# SCH_ESP-RotaryCell-Main-Carrier-Rev-A1_2.net
KiCad netlist of a schematic drawn in EasyEDA
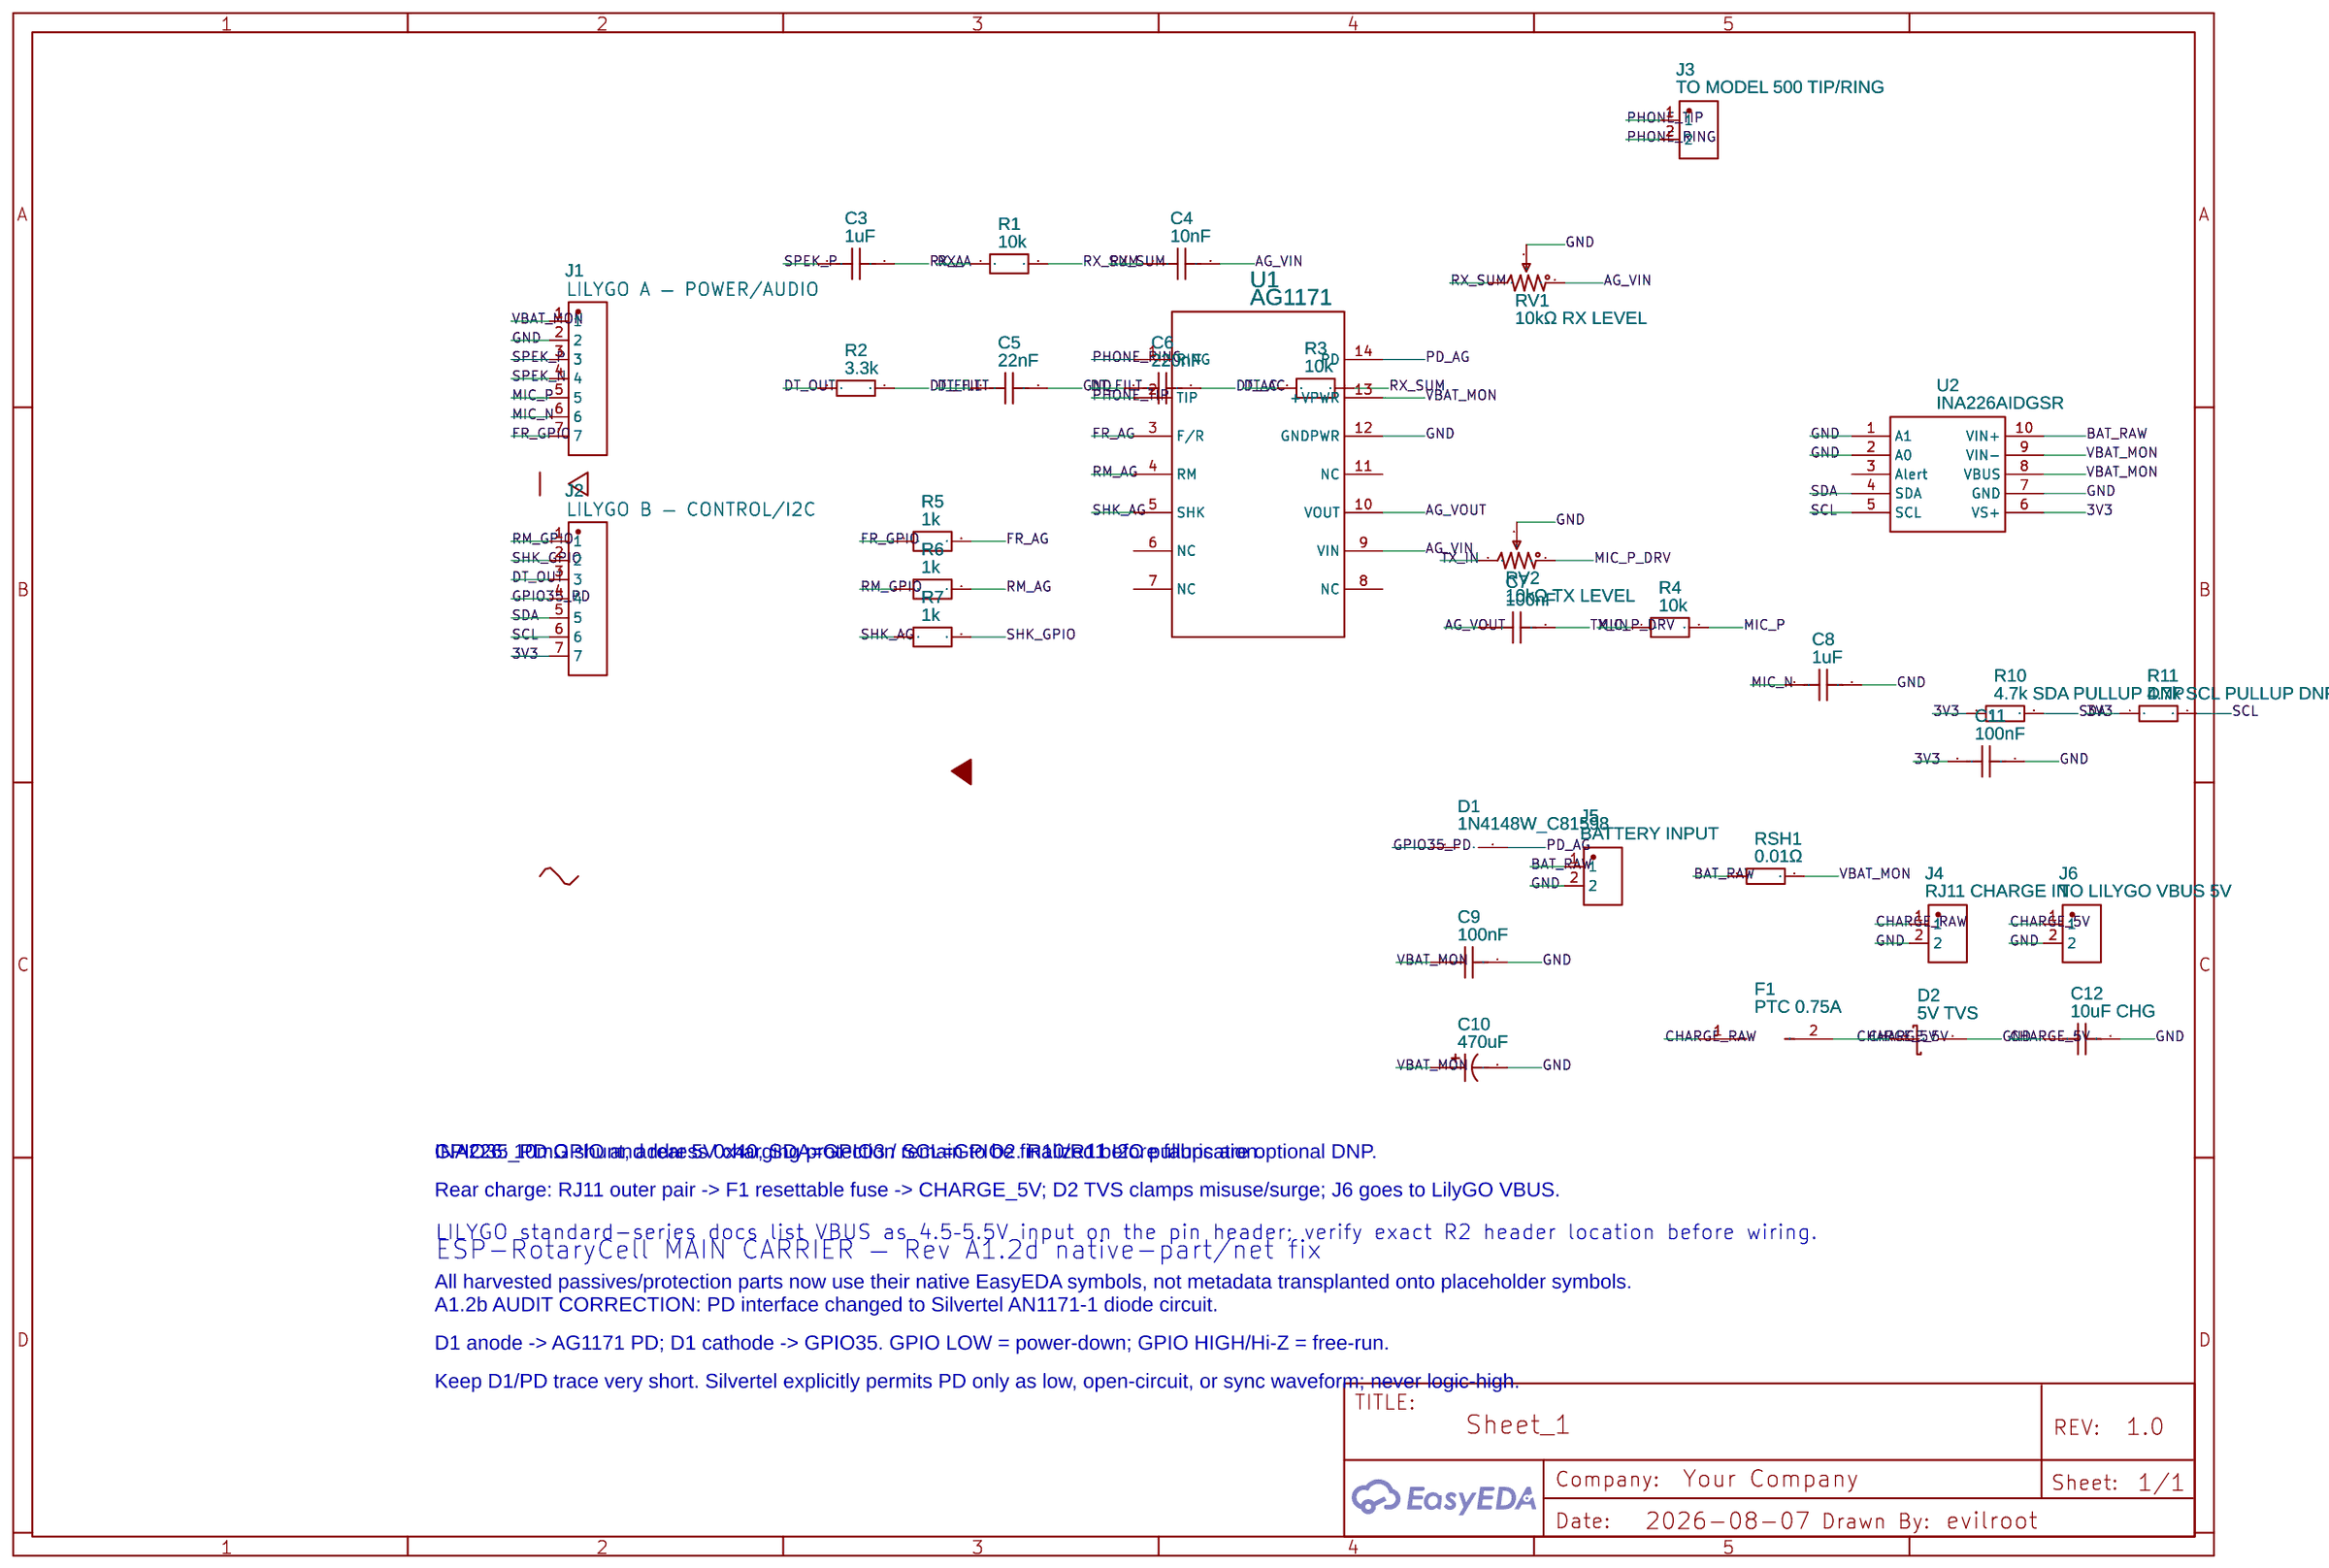
[diagram p0: schematic sheet]

(export (version "E")
  (design (tool "Eeschema 10.0.6"))
  (components
    (comp (ref "C3")
      (value "1uF")
      (fields
        (field (name "Manufacturer Part") "C0805C105K5RACAUTO")
        (field (name "Manufacturer") "KEMET(基美)")
      )
      (libsource (lib "") (part "C0805C105K5RACAUTO"))
    )
    (comp (ref "C4")
      (value "10nF")
      (fields
        (field (name "Manufacturer Part") "CGA0805X7R103J500KT")
        (field (name "Manufacturer") "HRE(芯声)")
      )
      (libsource (lib "") (part "CGA0805X7R103J500KT"))
    )
    (comp (ref "C5")
      (value "22nF")
      (fields
        (field (name "Manufacturer Part") "CGA0805C0G223J500MT")
        (field (name "Manufacturer") "HRE(芯声)")
      )
      (libsource (lib "") (part "CGA0805C0G223J500MT"))
    )
    (comp (ref "C6")
      (value "220nF")
      (fields
        (field (name "Manufacturer Part") "CGA0805X7R224K101MT")
        (field (name "Manufacturer") "HRE(芯声)")
      )
      (libsource (lib "") (part "CGA0805X7R224K101MT"))
    )
    (comp (ref "C7")
      (value "100nF")
      (fields
        (field (name "Manufacturer Part") "CAI0805X7R104K500KT")
        (field (name "Manufacturer") "HRE(芯声)")
      )
      (libsource (lib "") (part "CAI0805X7R104K500KT"))
    )
    (comp (ref "C8")
      (value "1uF")
      (fields
        (field (name "Manufacturer Part") "C0805C105K5RACAUTO")
        (field (name "Manufacturer") "KEMET(基美)")
      )
      (libsource (lib "") (part "C0805C105K5RACAUTO"))
    )
    (comp (ref "C9")
      (value "100nF")
      (fields
        (field (name "Manufacturer Part") "CAI0805X7R104K500KT")
        (field (name "Manufacturer") "HRE(芯声)")
      )
      (libsource (lib "") (part "CAI0805X7R104K500KT"))
    )
    (comp (ref "C10")
      (value "470uF")
      (fields
        (field (name "Manufacturer Part") "RYHT16V470UF5.5*11")
        (field (name "Manufacturer") "HONOR(荣誉)")
      )
      (libsource (lib "") (part "RYHT16V470UF5.5*11"))
    )
    (comp (ref "C11")
      (value "100nF")
      (fields
        (field (name "Manufacturer Part") "CAI0805X7R104K500KT")
        (field (name "Manufacturer") "HRE(芯声)")
      )
      (libsource (lib "") (part "CAI0805X7R104K500KT"))
    )
    (comp (ref "C12")
      (value "10uF CHG")
      (fields
        (field (name "Manufacturer Part") "CGA0805X5R106K160MT")
        (field (name "Manufacturer") "HRE(芯声)")
      )
      (libsource (lib "") (part "CGA0805X5R106K160MT"))
    )
    (comp (ref "D1")
      (value "1N4148W_C81598")
      (fields (field (name "Manufacturer Part") "1N4148W") (field (name "Manufacturer") "ST(先科)"))
      (libsource (lib "") (part "1N4148W_C81598"))
    )
    (comp (ref "D2")
      (value "5V TVS")
      (fields (field (name "Manufacturer Part") "SMA6.0A_TVS6V"))
      (libsource (lib "") (part "SMA6.0A_TVS6V"))
    )
    (comp (ref "F1")
      (value "PTC 0.75A")
      (fields (field (name "Manufacturer Part") "PPTCNANOSMDC075F-20.75A6V"))
      (libsource (lib "") (part "PPTCNANOSMDC075F-20.75A6V"))
    )
    (comp (ref "J1")
      (value "LILYGO A — POWER/AUDIO")
      (fields
        (field (name "Manufacturer Part") "PM2.54-1x7PZZ-H8.5")
        (field (name "Manufacturer") "SHOU HAN(首韩)")
      )
      (libsource (lib "") (part "PM2.54-1X7PZZ-H8.5"))
    )
    (comp (ref "J2")
      (value "LILYGO B — CONTROL/I2C")
      (fields
        (field (name "Manufacturer Part") "PM2.54-1x7PZZ-H8.5")
        (field (name "Manufacturer") "SHOU HAN(首韩)")
      )
      (libsource (lib "") (part "PM2.54-1X7PZZ-H8.5"))
    )
    (comp (ref "J3")
      (value "TO MODEL 500 TIP/RING")
      (fields
        (field (name "Manufacturer Part") "HMT-2.54-1*2PM")
        (field (name "Manufacturer") "HMTCONN(华明通)")
      )
      (libsource (lib "") (part "HMT-2.54-1*2PM"))
    )
    (comp (ref "J4")
      (value "RJ11 CHARGE IN")
      (fields
        (field (name "Manufacturer Part") "HMT-2.54-1*2PM")
        (field (name "Manufacturer") "HMTCONN(华明通)")
      )
      (libsource (lib "") (part "HMT-2.54-1*2PM"))
    )
    (comp (ref "J5")
      (value "BATTERY INPUT")
      (fields
        (field (name "Manufacturer Part") "HMT-2.54-1*2PM")
        (field (name "Manufacturer") "HMTCONN(华明通)")
      )
      (libsource (lib "") (part "HMT-2.54-1*2PM"))
    )
    (comp (ref "J6")
      (value "TO LILYGO VBUS 5V")
      (fields
        (field (name "Manufacturer Part") "HMT-2.54-1*2PM")
        (field (name "Manufacturer") "HMTCONN(华明通)")
      )
      (libsource (lib "") (part "HMT-2.54-1*2PM"))
    )
    (comp (ref "R1")
      (value "10k")
      (fields (field (name "Manufacturer Part") "RCS080510K0FKEA") (field (name "Manufacturer") "VISHAY(威世)"))
      (libsource (lib "") (part "RCS080510K0FKEA"))
    )
    (comp (ref "R2")
      (value "3.3k")
      (fields (field (name "Manufacturer Part") "RMC08053.3K1%N") (field (name "Manufacturer") "Tyohm(幸亚电阻)"))
      (libsource (lib "") (part "RMC08053.3K1%N"))
    )
    (comp (ref "R3")
      (value "10k")
      (fields (field (name "Manufacturer Part") "RCS080510K0FKEA") (field (name "Manufacturer") "VISHAY(威世)"))
      (libsource (lib "") (part "RCS080510K0FKEA"))
    )
    (comp (ref "R4")
      (value "10k")
      (fields (field (name "Manufacturer Part") "RCS080510K0FKEA") (field (name "Manufacturer") "VISHAY(威世)"))
      (libsource (lib "") (part "RCS080510K0FKEA"))
    )
    (comp (ref "R5")
      (value "1k")
      (fields (field (name "Manufacturer Part") "CL0805JN1KPS") (field (name "Manufacturer") "昶龙科技"))
      (libsource (lib "") (part "CL0805JN1KPS"))
    )
    (comp (ref "R6")
      (value "1k")
      (fields (field (name "Manufacturer Part") "CL0805JN1KPS") (field (name "Manufacturer") "昶龙科技"))
      (libsource (lib "") (part "CL0805JN1KPS"))
    )
    (comp (ref "R7")
      (value "1k")
      (fields (field (name "Manufacturer Part") "CL0805JN1KPS") (field (name "Manufacturer") "昶龙科技"))
      (libsource (lib "") (part "CL0805JN1KPS"))
    )
    (comp (ref "R10")
      (value "4.7k SDA PULLUP DNP")
      (fields (field (name "Manufacturer Part") "RMC08054.7K1%N") (field (name "Manufacturer") "Tyohm(幸亚电阻)"))
      (libsource (lib "") (part "RMC08054.7K1%N"))
    )
    (comp (ref "R11")
      (value "4.7k SCL PULLUP DNP")
      (fields (field (name "Manufacturer Part") "RMC08054.7K1%N") (field (name "Manufacturer") "Tyohm(幸亚电阻)"))
      (libsource (lib "") (part "RMC08054.7K1%N"))
    )
    (comp (ref "RSH1")
      (value "0.01Ω")
      (fields (field (name "Manufacturer Part") "MRF6432(2512)LR010JTS") (field (name "Manufacturer") "SUP"))
      (libsource (lib "") (part "MRF6432(2512)LR010JTS"))
    )
    (comp (ref "RV1")
      (value "10kΩ RX LEVEL")
      (fields (field (name "Manufacturer Part") "PS10KV50-103A3030") (field (name "Manufacturer") "Amphenol"))
      (libsource (lib "") (part "PS10KV50-103A3030"))
    )
    (comp (ref "RV2")
      (value "10kΩ TX LEVEL")
      (fields (field (name "Manufacturer Part") "PS10KV50-103A3030") (field (name "Manufacturer") "Amphenol"))
      (libsource (lib "") (part "PS10KV50-103A3030"))
    )
    (comp (ref "U1")
      (value "AG1171")
      (fields (field (name "Manufacturer Part") "Ag1171") (field (name "Manufacturer") "Silver Telecom"))
      (libsource (lib "") (part "AG1171"))
    )
    (comp (ref "U2")
      (value "INA226AIDGSR")
      (fields (field (name "Manufacturer") "TI(德州仪器)"))
      (libsource (lib "") (part "INA226AIDGSR"))
    )
  )
  (nets
    (net (code "1") (name "/3V3") (class "Default")
      (node (ref "C11") (pin "1") (pinfunction "1_1") (pintype "unspecified"))
      (node (ref "J2") (pin "7") (pinfunction "7_7") (pintype "unspecified"))
      (node (ref "R10") (pin "1") (pinfunction "1_1") (pintype "unspecified"))
      (node (ref "R11") (pin "1") (pinfunction "1_1") (pintype "unspecified"))
      (node (ref "U2") (pin "6") (pinfunction "VS+_6") (pintype "unspecified"))
    )
    (net (code "2") (name "/AG_VIN") (class "Default")
      (node (ref "C4") (pin "2") (pinfunction "2_2") (pintype "unspecified"))
      (node (ref "RV1") (pin "2") (pinfunction "2_2") (pintype "unspecified"))
      (node (ref "U1") (pin "9") (pinfunction "VIN_9") (pintype "unspecified"))
    )
    (net (code "3") (name "/AG_VOUT") (class "Default")
      (node (ref "C7") (pin "1") (pinfunction "1_1") (pintype "unspecified"))
      (node (ref "U1") (pin "10") (pinfunction "VOUT_10") (pintype "unspecified"))
    )
    (net (code "4") (name "/BAT_RAW") (class "Default")
      (node (ref "J5") (pin "1") (pinfunction "1_1") (pintype "unspecified"))
      (node (ref "RSH1") (pin "1") (pinfunction "1_1") (pintype "input"))
      (node (ref "U2") (pin "10") (pinfunction "VIN+_10") (pintype "unspecified"))
    )
    (net (code "5") (name "/CHARGE_5V") (class "Default")
      (node (ref "C12") (pin "1") (pinfunction "1_1") (pintype "unspecified"))
      (node (ref "D2") (pin "1") (pinfunction "C_1") (pintype "unspecified"))
      (node (ref "F1") (pin "2") (pinfunction "2_2") (pintype "unspecified"))
      (node (ref "J6") (pin "1") (pinfunction "1_1") (pintype "unspecified"))
    )
    (net (code "6") (name "/CHARGE_RAW") (class "Default")
      (node (ref "F1") (pin "1") (pinfunction "1_1") (pintype "unspecified"))
      (node (ref "J4") (pin "1") (pinfunction "1_1") (pintype "unspecified"))
    )
    (net (code "7") (name "/DT_AC") (class "Default")
      (node (ref "C6") (pin "2") (pinfunction "2_2") (pintype "unspecified"))
      (node (ref "R3") (pin "1") (pinfunction "1_1") (pintype "unspecified"))
    )
    (net (code "8") (name "/DT_FILT") (class "Default")
      (node (ref "C5") (pin "1") (pinfunction "1_1") (pintype "unspecified"))
      (node (ref "C6") (pin "1") (pinfunction "1_1") (pintype "unspecified"))
      (node (ref "R2") (pin "2") (pinfunction "2_2") (pintype "unspecified"))
    )
    (net (code "9") (name "/DT_OUT") (class "Default")
      (node (ref "J2") (pin "3") (pinfunction "3_3") (pintype "unspecified"))
      (node (ref "R2") (pin "1") (pinfunction "1_1") (pintype "unspecified"))
    )
    (net (code "10") (name "/FR_AG") (class "Default")
      (node (ref "R5") (pin "2") (pinfunction "2_2") (pintype "unspecified"))
      (node (ref "U1") (pin "3") (pinfunction "F/R_3") (pintype "unspecified"))
    )
    (net (code "11") (name "/FR_GPIO") (class "Default")
      (node (ref "J1") (pin "7") (pinfunction "7_7") (pintype "unspecified"))
      (node (ref "R5") (pin "1") (pinfunction "1_1") (pintype "unspecified"))
    )
    (net (code "12") (name "/GND") (class "Default")
      (node (ref "C10") (pin "2") (pinfunction "2_2") (pintype "input"))
      (node (ref "C11") (pin "2") (pinfunction "2_2") (pintype "unspecified"))
      (node (ref "C12") (pin "2") (pinfunction "2_2") (pintype "unspecified"))
      (node (ref "C5") (pin "2") (pinfunction "2_2") (pintype "unspecified"))
      (node (ref "C8") (pin "2") (pinfunction "2_2") (pintype "unspecified"))
      (node (ref "C9") (pin "2") (pinfunction "2_2") (pintype "unspecified"))
      (node (ref "D2") (pin "2") (pinfunction "A_2") (pintype "unspecified"))
      (node (ref "J1") (pin "2") (pinfunction "2_2") (pintype "unspecified"))
      (node (ref "J4") (pin "2") (pinfunction "2_2") (pintype "unspecified"))
      (node (ref "J5") (pin "2") (pinfunction "2_2") (pintype "unspecified"))
      (node (ref "J6") (pin "2") (pinfunction "2_2") (pintype "unspecified"))
      (node (ref "RV1") (pin "3") (pinfunction "3_3") (pintype "unspecified"))
      (node (ref "RV2") (pin "3") (pinfunction "3_3") (pintype "unspecified"))
      (node (ref "U1") (pin "12") (pinfunction "GNDPWR_12") (pintype "unspecified"))
      (node (ref "U2") (pin "1") (pinfunction "A1_1") (pintype "unspecified"))
      (node (ref "U2") (pin "2") (pinfunction "A0_2") (pintype "unspecified"))
      (node (ref "U2") (pin "7") (pinfunction "GND_7") (pintype "unspecified"))
    )
    (net (code "13") (name "/GPIO35_PD") (class "Default")
      (node (ref "D1") (pin "1") (pinfunction "K_1") (pintype "unspecified"))
      (node (ref "J2") (pin "4") (pinfunction "4_4") (pintype "unspecified"))
    )
    (net (code "14") (name "/MIC_N") (class "Default")
      (node (ref "C8") (pin "1") (pinfunction "1_1") (pintype "unspecified"))
      (node (ref "J1") (pin "6") (pinfunction "6_6") (pintype "unspecified"))
    )
    (net (code "15") (name "/MIC_P") (class "Default")
      (node (ref "J1") (pin "5") (pinfunction "5_5") (pintype "unspecified"))
      (node (ref "R4") (pin "2") (pinfunction "2_2") (pintype "unspecified"))
    )
    (net (code "16") (name "/MIC_P_DRV") (class "Default")
      (node (ref "R4") (pin "1") (pinfunction "1_1") (pintype "unspecified"))
      (node (ref "RV2") (pin "2") (pinfunction "2_2") (pintype "unspecified"))
    )
    (net (code "17") (name "/PD_AG") (class "Default")
      (node (ref "D1") (pin "2") (pinfunction "A_2") (pintype "unspecified"))
      (node (ref "U1") (pin "14") (pinfunction "PD_14") (pintype "unspecified"))
    )
    (net (code "18") (name "/PHONE_RING") (class "Default")
      (node (ref "J3") (pin "2") (pinfunction "2_2") (pintype "unspecified"))
      (node (ref "U1") (pin "1") (pinfunction "RING_1") (pintype "unspecified"))
    )
    (net (code "19") (name "/PHONE_TIP") (class "Default")
      (node (ref "J3") (pin "1") (pinfunction "1_1") (pintype "unspecified"))
      (node (ref "U1") (pin "2") (pinfunction "TIP_2") (pintype "unspecified"))
    )
    (net (code "20") (name "/RM_AG") (class "Default")
      (node (ref "R6") (pin "2") (pinfunction "2_2") (pintype "unspecified"))
      (node (ref "U1") (pin "4") (pinfunction "RM_4") (pintype "unspecified"))
    )
    (net (code "21") (name "/RM_GPIO") (class "Default")
      (node (ref "J2") (pin "1") (pinfunction "1_1") (pintype "unspecified"))
      (node (ref "R6") (pin "1") (pinfunction "1_1") (pintype "unspecified"))
    )
    (net (code "22") (name "/RX_A") (class "Default")
      (node (ref "C3") (pin "2") (pinfunction "2_2") (pintype "unspecified"))
      (node (ref "R1") (pin "1") (pinfunction "1_1") (pintype "unspecified"))
    )
    (net (code "23") (name "/RX_SUM") (class "Default")
      (node (ref "C4") (pin "1") (pinfunction "1_1") (pintype "unspecified"))
      (node (ref "R1") (pin "2") (pinfunction "2_2") (pintype "unspecified"))
      (node (ref "R3") (pin "2") (pinfunction "2_2") (pintype "unspecified"))
      (node (ref "RV1") (pin "1") (pinfunction "1_1") (pintype "unspecified"))
    )
    (net (code "24") (name "/SCL") (class "Default")
      (node (ref "J2") (pin "6") (pinfunction "6_6") (pintype "unspecified"))
      (node (ref "R11") (pin "2") (pinfunction "2_2") (pintype "unspecified"))
      (node (ref "U2") (pin "5") (pinfunction "SCL_5") (pintype "unspecified"))
    )
    (net (code "25") (name "/SDA") (class "Default")
      (node (ref "J2") (pin "5") (pinfunction "5_5") (pintype "unspecified"))
      (node (ref "R10") (pin "2") (pinfunction "2_2") (pintype "unspecified"))
      (node (ref "U2") (pin "4") (pinfunction "SDA_4") (pintype "unspecified"))
    )
    (net (code "26") (name "/SHK_AG") (class "Default")
      (node (ref "R7") (pin "1") (pinfunction "1_1") (pintype "unspecified"))
      (node (ref "U1") (pin "5") (pinfunction "SHK_5") (pintype "unspecified"))
    )
    (net (code "27") (name "/SHK_GPIO") (class "Default")
      (node (ref "J2") (pin "2") (pinfunction "2_2") (pintype "unspecified"))
      (node (ref "R7") (pin "2") (pinfunction "2_2") (pintype "unspecified"))
    )
    (net (code "28") (name "/SPEK_N") (class "Default")
      (node (ref "J1") (pin "4") (pinfunction "4_4") (pintype "unspecified"))
    )
    (net (code "29") (name "/SPEK_P") (class "Default")
      (node (ref "C3") (pin "1") (pinfunction "1_1") (pintype "unspecified"))
      (node (ref "J1") (pin "3") (pinfunction "3_3") (pintype "unspecified"))
    )
    (net (code "30") (name "/TX_IN") (class "Default")
      (node (ref "C7") (pin "2") (pinfunction "2_2") (pintype "unspecified"))
      (node (ref "RV2") (pin "1") (pinfunction "1_1") (pintype "unspecified"))
    )
    (net (code "31") (name "/VBAT_MON") (class "Default")
      (node (ref "C10") (pin "1") (pinfunction "1_1") (pintype "input"))
      (node (ref "C9") (pin "1") (pinfunction "1_1") (pintype "unspecified"))
      (node (ref "J1") (pin "1") (pinfunction "1_1") (pintype "unspecified"))
      (node (ref "RSH1") (pin "2") (pinfunction "2_2") (pintype "input"))
      (node (ref "U1") (pin "13") (pinfunction "+VPWR_13") (pintype "unspecified"))
      (node (ref "U2") (pin "8") (pinfunction "VBUS_8") (pintype "unspecified"))
      (node (ref "U2") (pin "9") (pinfunction "VIN-_9") (pintype "unspecified"))
    )
    (net (code "32") (name "unconnected-(U1-NC-Pad6)") (class "Default")
      (node (ref "U1") (pin "6") (pinfunction "NC_6") (pintype "unspecified"))
    )
    (net (code "33") (name "unconnected-(U1-NC-Pad7)") (class "Default")
      (node (ref "U1") (pin "7") (pinfunction "NC_7") (pintype "unspecified"))
    )
    (net (code "34") (name "unconnected-(U1-NC-Pad8)") (class "Default")
      (node (ref "U1") (pin "8") (pinfunction "NC_8") (pintype "unspecified"))
    )
    (net (code "35") (name "unconnected-(U1-NC-Pad11)") (class "Default")
      (node (ref "U1") (pin "11") (pinfunction "NC_11") (pintype "unspecified"))
    )
    (net (code "36") (name "unconnected-(U2-Alert-Pad3)") (class "Default")
      (node (ref "U2") (pin "3") (pinfunction "Alert_3") (pintype "unspecified"))
    )
  )
)
